# volume.net
KiCad netlist of a schematic drawn in EAGLE
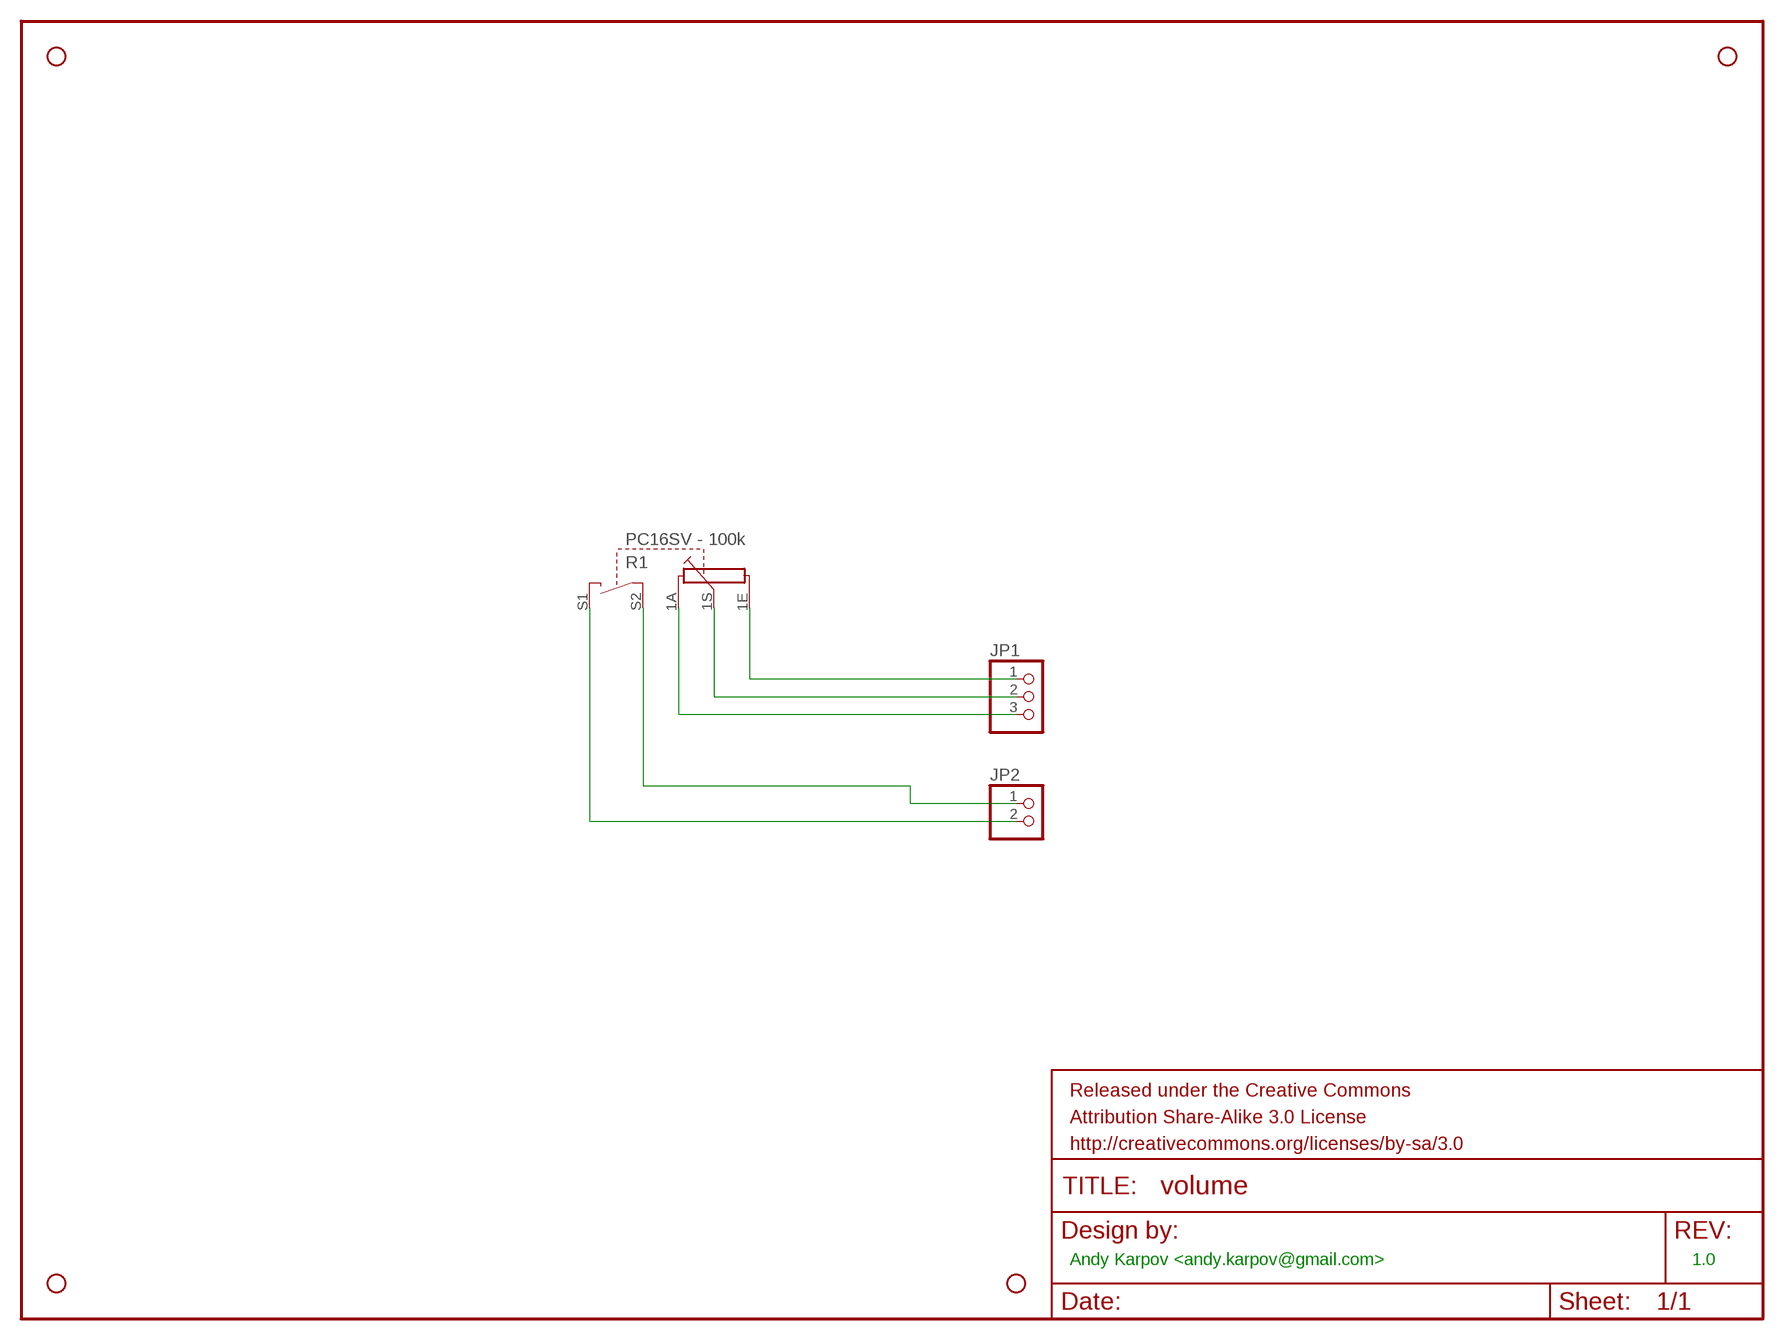
[diagram p0: schematic, sheet 1]

(export (version "E")
  (design (tool "Eeschema 10.0.6"))
  (components
    (comp (ref "FRAME1")
      (value "FRAME-LETTER")
      (footprint "eagle-import:CREATIVE_COMMONS")
      (libsource (lib "eagle-import") (part "FRAME-LETTER"))
    )
    (comp (ref "JP1")
      (value "PINHD-1X3")
      (footprint "eagle-import:1X03")
      (libsource (lib "eagle-import") (part "PINHD-1X3"))
    )
    (comp (ref "JP2")
      (value "PINHD-1X2")
      (footprint "eagle-import:1X02")
      (libsource (lib "eagle-import") (part "PINHD-1X2"))
    )
    (comp (ref "R1")
      (value "PC16SV - 100k")
      (footprint "eagle-import:PC16SV")
      (libsource (lib "eagle-import") (part "PC16SV"))
    )
    (comp (ref "STANDOFF1")
      (value "STAND-OFF")
      (footprint "eagle-import:STAND-OFF")
      (libsource (lib "eagle-import") (part "STAND-OFF"))
    )
    (comp (ref "STANDOFF2")
      (value "STAND-OFF")
      (footprint "eagle-import:STAND-OFF")
      (libsource (lib "eagle-import") (part "STAND-OFF"))
    )
    (comp (ref "STANDOFF3")
      (value "STAND-OFF")
      (footprint "eagle-import:STAND-OFF")
      (libsource (lib "eagle-import") (part "STAND-OFF"))
    )
    (comp (ref "STANDOFF4")
      (value "STAND-OFF")
      (footprint "eagle-import:STAND-OFF")
      (libsource (lib "eagle-import") (part "STAND-OFF"))
    )
  )
  (nets
    (net (code "1") (name "Net-(JP1-Pad1)") (class "Default")
      (node (ref "JP1") (pin "1") (pinfunction "1_1") (pintype "passive"))
      (node (ref "R1") (pin "1E") (pinfunction "1E_1E") (pintype "passive"))
    )
    (net (code "2") (name "Net-(JP1-Pad2)") (class "Default")
      (node (ref "JP1") (pin "2") (pinfunction "2_2") (pintype "passive"))
      (node (ref "R1") (pin "1S") (pinfunction "1S_1S") (pintype "passive"))
    )
    (net (code "3") (name "Net-(JP1-Pad3)") (class "Default")
      (node (ref "JP1") (pin "3") (pinfunction "3_3") (pintype "passive"))
      (node (ref "R1") (pin "1A") (pinfunction "1A_1A") (pintype "passive"))
    )
    (net (code "4") (name "Net-(JP2-Pad1)") (class "Default")
      (node (ref "JP2") (pin "1") (pinfunction "1_1") (pintype "passive"))
      (node (ref "R1") (pin "S2") (pinfunction "S2_S2") (pintype "passive"))
    )
    (net (code "5") (name "Net-(JP2-Pad2)") (class "Default")
      (node (ref "JP2") (pin "2") (pinfunction "2_2") (pintype "passive"))
      (node (ref "R1") (pin "S1") (pinfunction "S1_S1") (pintype "passive"))
    )
  )
)
